# Digital_Clock_Backup_SCH.net
KiCad netlist of a schematic drawn in Altium Designer
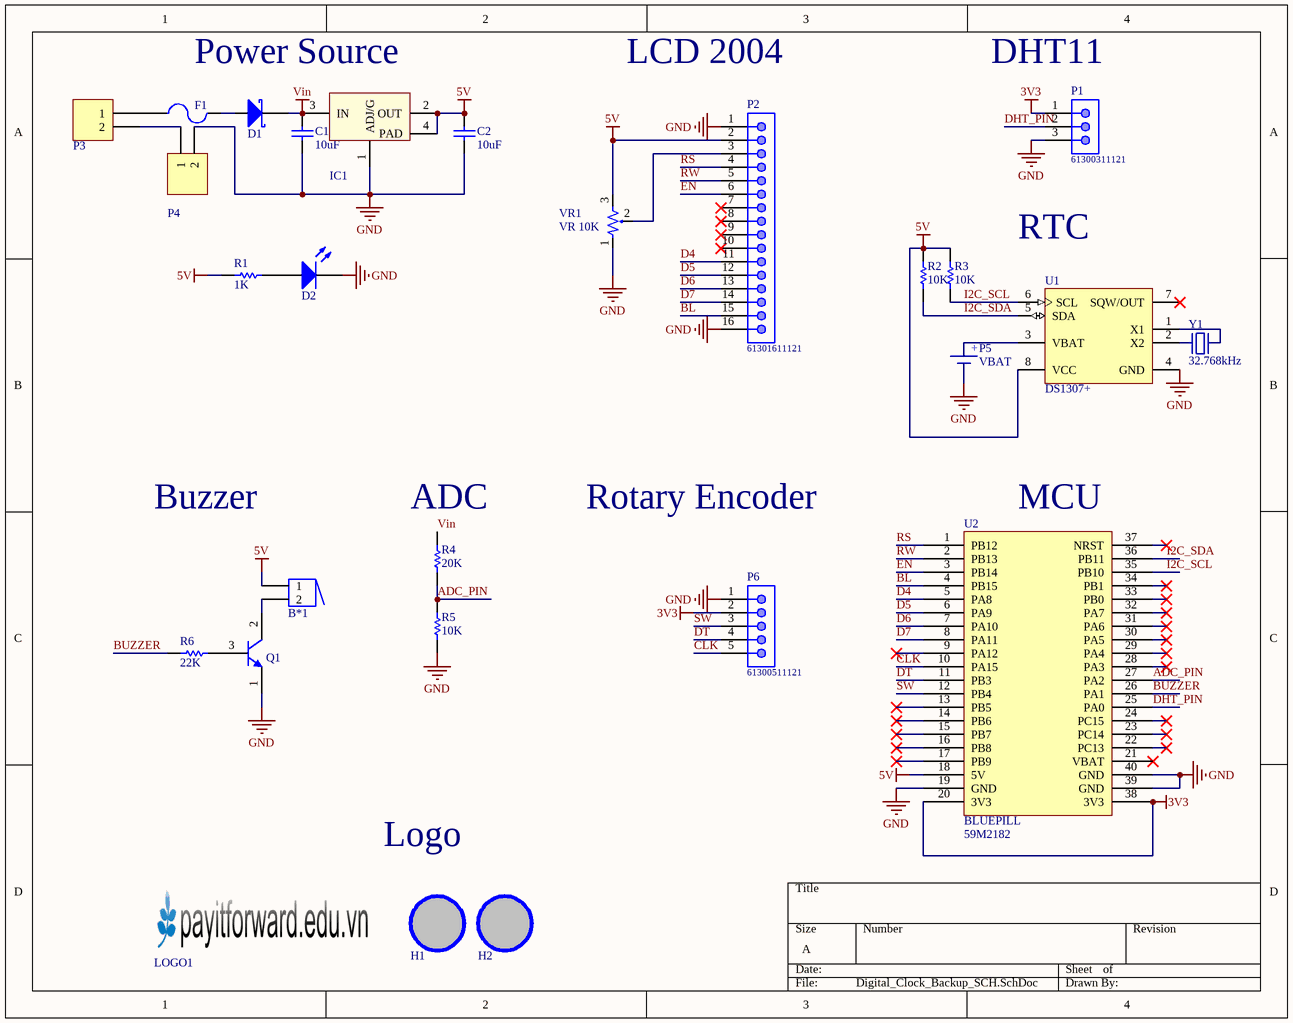
[diagram p0: Digital_Clock_Backup_SCH.SchDoc]

(export (version "E")
  (design (tool "Eeschema 10.0.6"))
  (components
    (comp (ref "B*1") (value "Buzzer") (footprint "BUZZER") (libsource (lib "PIF_Library") (part "Buzzer")))
    (comp (ref "C1")
      (value "10uF")
      (footprint "CAP-SM-0805")
      (description "Capacitor")
      (fields (field (name "Comment") "Cap Non-Pol SMD"))
      (libsource (lib "PIF_Library") (part "Cap Non-Pol SMD"))
    )
    (comp (ref "C2")
      (value "10uF")
      (footprint "CAP-SM-0805")
      (description "Capacitor")
      (fields (field (name "Comment") "Cap Non-Pol SMD"))
      (libsource (lib "PIF_Library") (part "Cap Non-Pol SMD"))
    )
    (comp (ref "D1")
      (value "D Schottky")
      (footprint "SS34")
      (description "Schottky Diode")
      (fields (field (name "PUBLISHER") "Altium Limited"))
      (libsource (lib "PIF_Library") (part "D Schottky"))
    )
    (comp (ref "D2") (value "LED") (footprint "LED-3mm") (libsource (lib "PIF_Library") (part "LED")))
    (comp (ref "F1") (value "Fuse") (footprint "FUSE SMD") (libsource (lib "PIF_Library") (part "Fuse")))
    (comp (ref "H1")
      (value "Hole")
      (footprint "LO KHOAN 3MM")
      (description "Hole 3mm")
      (libsource (lib "PIF_Library") (part "Hole"))
    )
    (comp (ref "H2")
      (value "Hole")
      (footprint "LO KHOAN 3MM")
      (description "Hole 3mm")
      (libsource (lib "PIF_Library") (part "Hole"))
    )
    (comp (ref "IC1")
      (value "LM1117")
      (footprint "SOT223-4N")
      (description "Available in 1.8V, 2.5V, 2.85V, 3.3V, 5V, and  Adjustable Versions")
      (libsource (lib "PIF_Library") (part "LM1117"))
    )
    (comp (ref "LOGO1")
      (value "LOGO PIF")
      (footprint "PIF LOGO SMALL TOP")
      (libsource (lib "PIF_Library") (part "LOGO PIF"))
    )
    (comp (ref "P1")
      (value "61300311121")
      (footprint "61300311121")
      (description "WR-PHD Pin Header, THT, pitch 2.54mm, Single Row, Vertical, 3p")
      (fields (field (name "MANUFACTURER") "Wurth Elektronik"))
      (libsource (lib "Altium_WR-PHD (rev20a)") (part "61300311121"))
    )
    (comp (ref "P2")
      (value "61301611121")
      (footprint "61301611121")
      (description "WR-PHD Pin Header, THT, pitch 2.54mm, Single Row, Vertical, 16p")
      (fields (field (name "MANUFACTURER") "Wurth Elektronik"))
      (libsource (lib "Altium_WR-PHD (rev20a)") (part "61301611121"))
    )
    (comp (ref "P3")
      (value "Domino 2")
      (footprint "DOMINO SMALL 2")
      (description "Domino, 2-Pin")
      (fields (field (name "PUBLISHER") "Altium Limited"))
      (libsource (lib "PIF_Library") (part "Domino 2"))
    )
    (comp (ref "P4")
      (value "Domino 2")
      (footprint "DOMINO SMALL 2")
      (description "Domino, 2-Pin")
      (fields (field (name "PUBLISHER") "Altium Limited"))
      (libsource (lib "") (part "Domino 2_1"))
    )
    (comp (ref "P5")
      (value "VBAT")
      (footprint "VBAT CR2030")
      (description "CR2032")
      (fields
        (field (name "MANUFACTURER") "DANTONA INDUSTRIES")
        (field (name "MANUFACTURER PART NUMBER") "CR2032 SANYO")
      )
      (libsource (lib "Digital_Clock") (part "VBAT CR2032"))
    )
    (comp (ref "P6")
      (value "61300511121")
      (footprint "61300511121")
      (description "WR-PHD Pin Header, THT, pitch 2.54mm, Single Row, Vertical, 5p")
      (fields (field (name "MANUFACTURER") "Wurth Elektronik"))
      (libsource (lib "Altium_WR-PHD (rev20a)") (part "61300511121"))
    )
    (comp (ref "Q1")
      (value "C1815")
      (footprint "SOT23B")
      (description "NPN Bipolar Transistor")
      (libsource (lib "PIF_Library") (part "C1815"))
    )
    (comp (ref "R1")
      (value "1K")
      (footprint "RES-SM-0805")
      (description "Resistor")
      (fields (field (name "Comment") "RESISTOR SMD"))
      (libsource (lib "PIF_Library") (part "RESISTOR SMD"))
    )
    (comp (ref "R2")
      (value "10K")
      (footprint "RES-SM-0805")
      (description "Resistor")
      (fields (field (name "Comment") "RESISTOR SMD"))
      (libsource (lib "PIF_Library") (part "RESISTOR SMD"))
    )
    (comp (ref "R3")
      (value "10K")
      (footprint "RES-SM-0805")
      (description "Resistor")
      (fields (field (name "Comment") "RESISTOR SMD"))
      (libsource (lib "PIF_Library") (part "RESISTOR SMD"))
    )
    (comp (ref "R4")
      (value "20K")
      (footprint "RES-SM-0805")
      (description "Resistor")
      (fields (field (name "Comment") "RESISTOR SMD"))
      (libsource (lib "PIF_Library") (part "RESISTOR SMD"))
    )
    (comp (ref "R5")
      (value "10K")
      (footprint "RES-SM-0805")
      (description "Resistor")
      (fields (field (name "Comment") "RESISTOR SMD"))
      (libsource (lib "PIF_Library") (part "RESISTOR SMD"))
    )
    (comp (ref "R6")
      (value "22K")
      (footprint "RES-SM-0805")
      (description "Resistor")
      (fields (field (name "Comment") "RESISTOR SMD"))
      (libsource (lib "PIF_Library") (part "RESISTOR SMD"))
    )
    (comp (ref "U1")
      (value "DS1307+")
      (footprint "MAXM-P8-1")
      (description "I2C Real-Time Clock, 5 V, 0 to 70 degC, 8-Pin DIP, RoHS, Tube")
      (fields (field (name "MANUFACTURER") "Maxim"))
      (libsource (lib "HCMUT") (part "MAXM-DS1307Z+-8"))
    )
    (comp (ref "U2")
      (value "BLUEPILL")
      (footprint "BLUEPILL")
      (description "Development board STM32F103C8T6")
      (fields (field (name "SUPPLIER PART NUMBER 1") "59M2182"))
      (libsource (lib "Giang's Libs") (part "BLUEPILL"))
    )
    (comp (ref "VR1")
      (value "VR 10K")
      (footprint "Varistor 1")
      (description "Var Resistor")
      (fields (field (name "Comment") "10K"))
      (libsource (lib "PIF_Library") (part "Var Resistor"))
    )
    (comp (ref "Y1")
      (value "32.768kHz")
      (footprint "XTAL 32768 3x8")
      (description "Crystal For all Crystal 2pin")
      (libsource (lib "Digital_Clock") (part "XTAL"))
    )
  )
  (nets
    (net (code "1") (name "/ADC_PIN") (class "Default")
      (node (ref "R4") (pin "1") (pinfunction "1_1") (pintype "passive"))
      (node (ref "R5") (pin "2") (pinfunction "2_2") (pintype "passive"))
      (node (ref "U2") (pin "27") (pinfunction "PA2_27") (pintype "passive"))
    )
    (net (code "2") (name "/BL") (class "Default")
      (node (ref "P2") (pin "15") (pinfunction "15_15") (pintype "passive"))
      (node (ref "U2") (pin "4") (pinfunction "PB15_4") (pintype "passive"))
    )
    (net (code "3") (name "/BUZZER") (class "Default")
      (node (ref "R6") (pin "1") (pinfunction "1_1") (pintype "passive"))
      (node (ref "U2") (pin "26") (pinfunction "PA1_26") (pintype "passive"))
    )
    (net (code "4") (name "/CLK") (class "Default")
      (node (ref "P6") (pin "5") (pinfunction "5_5") (pintype "passive"))
      (node (ref "U2") (pin "10") (pinfunction "PA15_10") (pintype "passive"))
    )
    (net (code "5") (name "/D4") (class "Default")
      (node (ref "P2") (pin "11") (pinfunction "11_11") (pintype "passive"))
      (node (ref "U2") (pin "5") (pinfunction "PA8_5") (pintype "passive"))
    )
    (net (code "6") (name "/D5") (class "Default")
      (node (ref "P2") (pin "12") (pinfunction "12_12") (pintype "passive"))
      (node (ref "U2") (pin "6") (pinfunction "PA9_6") (pintype "passive"))
    )
    (net (code "7") (name "/D6") (class "Default")
      (node (ref "P2") (pin "13") (pinfunction "13_13") (pintype "passive"))
      (node (ref "U2") (pin "7") (pinfunction "PA10_7") (pintype "passive"))
    )
    (net (code "8") (name "/D7") (class "Default")
      (node (ref "P2") (pin "14") (pinfunction "14_14") (pintype "passive"))
      (node (ref "U2") (pin "8") (pinfunction "PA11_8") (pintype "passive"))
    )
    (net (code "9") (name "/DHT_PIN") (class "Default")
      (node (ref "P1") (pin "2") (pinfunction "2_2") (pintype "passive"))
      (node (ref "U2") (pin "25") (pinfunction "PA0_25") (pintype "passive"))
    )
    (net (code "10") (name "/DT") (class "Default")
      (node (ref "P6") (pin "4") (pinfunction "4_4") (pintype "passive"))
      (node (ref "U2") (pin "11") (pinfunction "PB3_11") (pintype "passive"))
    )
    (net (code "11") (name "/EN") (class "Default")
      (node (ref "P2") (pin "6") (pinfunction "6_6") (pintype "passive"))
      (node (ref "U2") (pin "3") (pinfunction "PB14_3") (pintype "passive"))
    )
    (net (code "12") (name "/I2C_SCL") (class "Default")
      (node (ref "R3") (pin "1") (pinfunction "1_1") (pintype "passive"))
      (node (ref "U1") (pin "6") (pinfunction "SCL_6") (pintype "input"))
      (node (ref "U2") (pin "35") (pinfunction "PB10_35") (pintype "passive"))
    )
    (net (code "13") (name "/I2C_SDA") (class "Default")
      (node (ref "R2") (pin "1") (pinfunction "1_1") (pintype "passive"))
      (node (ref "U1") (pin "5") (pinfunction "SDA_5") (pintype "bidirectional"))
      (node (ref "U2") (pin "36") (pinfunction "PB11_36") (pintype "passive"))
    )
    (net (code "14") (name "/RS") (class "Default")
      (node (ref "P2") (pin "4") (pinfunction "4_4") (pintype "passive"))
      (node (ref "U2") (pin "1") (pinfunction "PB12_1") (pintype "passive"))
    )
    (net (code "15") (name "/RW") (class "Default")
      (node (ref "P2") (pin "5") (pinfunction "5_5") (pintype "passive"))
      (node (ref "U2") (pin "2") (pinfunction "PB13_2") (pintype "passive"))
    )
    (net (code "16") (name "/SW") (class "Default")
      (node (ref "P6") (pin "3") (pinfunction "3_3") (pintype "passive"))
      (node (ref "U2") (pin "12") (pinfunction "PB4_12") (pintype "passive"))
    )
    (net (code "17") (name "3V3") (class "Default")
      (node (ref "P1") (pin "1") (pinfunction "1_1") (pintype "passive"))
      (node (ref "P6") (pin "2") (pinfunction "2_2") (pintype "passive"))
      (node (ref "U2") (pin "20") (pinfunction "3V3_20") (pintype "passive"))
      (node (ref "U2") (pin "38") (pinfunction "3V3_38") (pintype "passive"))
    )
    (net (code "18") (name "5V") (class "Default")
      (node (ref "B*1") (pin "1") (pinfunction "1_1") (pintype "passive"))
      (node (ref "C2") (pin "2") (pinfunction "2_2") (pintype "passive"))
      (node (ref "IC1") (pin "2") (pinfunction "OUT_2") (pintype "passive"))
      (node (ref "IC1") (pin "4") (pinfunction "PAD_4") (pintype "passive"))
      (node (ref "P2") (pin "2") (pinfunction "2_2") (pintype "passive"))
      (node (ref "R1") (pin "1") (pinfunction "1_1") (pintype "passive"))
      (node (ref "R2") (pin "2") (pinfunction "2_2") (pintype "passive"))
      (node (ref "R3") (pin "2") (pinfunction "2_2") (pintype "passive"))
      (node (ref "U1") (pin "8") (pinfunction "VCC_8") (pintype "power_in"))
      (node (ref "U2") (pin "18") (pinfunction "5V_18") (pintype "passive"))
      (node (ref "VR1") (pin "3") (pinfunction "3_3") (pintype "passive"))
    )
    (net (code "19") (name "GND") (class "Default")
      (node (ref "C1") (pin "1") (pinfunction "1_1") (pintype "passive"))
      (node (ref "C2") (pin "1") (pinfunction "1_1") (pintype "passive"))
      (node (ref "D2") (pin "2") (pinfunction "K_2") (pintype "passive"))
      (node (ref "IC1") (pin "1") (pinfunction "ADJ/G_1") (pintype "passive"))
      (node (ref "P1") (pin "3") (pinfunction "3_3") (pintype "passive"))
      (node (ref "P2") (pin "1") (pinfunction "1_1") (pintype "passive"))
      (node (ref "P2") (pin "16") (pinfunction "16_16") (pintype "passive"))
      (node (ref "P4") (pin "2") (pinfunction "2_2") (pintype "passive"))
      (node (ref "P5") (pin "2") (pinfunction "+_2") (pintype "passive"))
      (node (ref "P6") (pin "1") (pinfunction "1_1") (pintype "passive"))
      (node (ref "Q1") (pin "1") (pinfunction "E_1") (pintype "passive"))
      (node (ref "R5") (pin "1") (pinfunction "1_1") (pintype "passive"))
      (node (ref "U1") (pin "4") (pinfunction "GND_4") (pintype "power_in"))
      (node (ref "U2") (pin "19") (pinfunction "GND_19") (pintype "passive"))
      (node (ref "U2") (pin "39") (pinfunction "GND_39") (pintype "passive"))
      (node (ref "U2") (pin "40") (pinfunction "GND_40") (pintype "passive"))
      (node (ref "VR1") (pin "1") (pinfunction "1_1") (pintype "passive"))
    )
    (net (code "20") (name "Net-(D1-A)") (class "Default")
      (node (ref "D1") (pin "1") (pinfunction "A_1") (pintype "passive"))
      (node (ref "F1") (pin "2") (pinfunction "2_2") (pintype "passive"))
    )
    (net (code "21") (name "Net-(D2-A)") (class "Default")
      (node (ref "D2") (pin "1") (pinfunction "A_1") (pintype "passive"))
      (node (ref "R1") (pin "2") (pinfunction "2_2") (pintype "passive"))
    )
    (net (code "22") (name "Net-(F1-Pad1)") (class "Default")
      (node (ref "F1") (pin "1") (pinfunction "1_1") (pintype "passive"))
      (node (ref "P3") (pin "1") (pinfunction "1_1") (pintype "passive"))
    )
    (net (code "23") (name "Net-(P2-Pad3)") (class "Default")
      (node (ref "P2") (pin "3") (pinfunction "3_3") (pintype "passive"))
      (node (ref "VR1") (pin "2") (pinfunction "2_2") (pintype "passive"))
    )
    (net (code "24") (name "Net-(P3-Pad2)") (class "Default")
      (node (ref "P3") (pin "2") (pinfunction "2_2") (pintype "passive"))
      (node (ref "P4") (pin "1") (pinfunction "1_1") (pintype "passive"))
    )
    (net (code "25") (name "Net-(Q1-B)") (class "Default")
      (node (ref "Q1") (pin "3") (pinfunction "B_3") (pintype "passive"))
      (node (ref "R6") (pin "2") (pinfunction "2_2") (pintype "passive"))
    )
    (net (code "26") (name "Net-(Q1-C)") (class "Default")
      (node (ref "B*1") (pin "2") (pinfunction "2_2") (pintype "passive"))
      (node (ref "Q1") (pin "2") (pinfunction "C_2") (pintype "passive"))
    )
    (net (code "27") (name "Net-(U1-VBAT)") (class "Default")
      (node (ref "P5") (pin "1") (pinfunction "+_1") (pintype "passive"))
      (node (ref "U1") (pin "3") (pinfunction "VBAT_3") (pintype "power_in"))
    )
    (net (code "28") (name "Net-(U1-X1)") (class "Default")
      (node (ref "U1") (pin "1") (pinfunction "X1_1") (pintype "passive"))
      (node (ref "Y1") (pin "2") (pinfunction "2_2") (pintype "passive"))
    )
    (net (code "29") (name "Net-(U1-X2)") (class "Default")
      (node (ref "U1") (pin "2") (pinfunction "X2_2") (pintype "passive"))
      (node (ref "Y1") (pin "1") (pinfunction "1_1") (pintype "passive"))
    )
    (net (code "30") (name "Vin") (class "Default")
      (node (ref "C1") (pin "2") (pinfunction "2_2") (pintype "passive"))
      (node (ref "D1") (pin "2") (pinfunction "K_2") (pintype "passive"))
      (node (ref "IC1") (pin "3") (pinfunction "IN_3") (pintype "passive"))
      (node (ref "R4") (pin "2") (pinfunction "2_2") (pintype "passive"))
    )
    (net (code "31") (name "unconnected-(H1-Pad1)") (class "Default")
      (node (ref "H1") (pin "1") (pinfunction "1_1") (pintype "passive"))
    )
    (net (code "32") (name "unconnected-(H2-Pad1)") (class "Default")
      (node (ref "H2") (pin "1") (pinfunction "1_1") (pintype "passive"))
    )
    (net (code "33") (name "unconnected-(P2-Pad7)") (class "Default")
      (node (ref "P2") (pin "7") (pinfunction "7_7") (pintype "passive+no_connect"))
    )
    (net (code "34") (name "unconnected-(P2-Pad8)") (class "Default")
      (node (ref "P2") (pin "8") (pinfunction "8_8") (pintype "passive+no_connect"))
    )
    (net (code "35") (name "unconnected-(P2-Pad9)") (class "Default")
      (node (ref "P2") (pin "9") (pinfunction "9_9") (pintype "passive+no_connect"))
    )
    (net (code "36") (name "unconnected-(P2-Pad10)") (class "Default")
      (node (ref "P2") (pin "10") (pinfunction "10_10") (pintype "passive+no_connect"))
    )
    (net (code "37") (name "unconnected-(U1-SQW{slash}OUT-Pad7)") (class "Default")
      (node (ref "U1") (pin "7") (pinfunction "SQW/OUT_7") (pintype "open_collector+no_connect"))
    )
    (net (code "38") (name "unconnected-(U2-NRST-Pad37)") (class "Default")
      (node (ref "U2") (pin "37") (pinfunction "NRST_37") (pintype "passive+no_connect"))
    )
    (net (code "39") (name "unconnected-(U2-PA3-Pad28)") (class "Default")
      (node (ref "U2") (pin "28") (pinfunction "PA3_28") (pintype "passive+no_connect"))
    )
    (net (code "40") (name "unconnected-(U2-PA4-Pad29)") (class "Default")
      (node (ref "U2") (pin "29") (pinfunction "PA4_29") (pintype "passive+no_connect"))
    )
    (net (code "41") (name "unconnected-(U2-PA5-Pad30)") (class "Default")
      (node (ref "U2") (pin "30") (pinfunction "PA5_30") (pintype "passive+no_connect"))
    )
    (net (code "42") (name "unconnected-(U2-PA6-Pad31)") (class "Default")
      (node (ref "U2") (pin "31") (pinfunction "PA6_31") (pintype "passive+no_connect"))
    )
    (net (code "43") (name "unconnected-(U2-PA7-Pad32)") (class "Default")
      (node (ref "U2") (pin "32") (pinfunction "PA7_32") (pintype "passive+no_connect"))
    )
    (net (code "44") (name "unconnected-(U2-PA12-Pad9)") (class "Default")
      (node (ref "U2") (pin "9") (pinfunction "PA12_9") (pintype "passive+no_connect"))
    )
    (net (code "45") (name "unconnected-(U2-PB0-Pad33)") (class "Default")
      (node (ref "U2") (pin "33") (pinfunction "PB0_33") (pintype "passive+no_connect"))
    )
    (net (code "46") (name "unconnected-(U2-PB1-Pad34)") (class "Default")
      (node (ref "U2") (pin "34") (pinfunction "PB1_34") (pintype "passive+no_connect"))
    )
    (net (code "47") (name "unconnected-(U2-PB5-Pad13)") (class "Default")
      (node (ref "U2") (pin "13") (pinfunction "PB5_13") (pintype "passive+no_connect"))
    )
    (net (code "48") (name "unconnected-(U2-PB6-Pad14)") (class "Default")
      (node (ref "U2") (pin "14") (pinfunction "PB6_14") (pintype "passive+no_connect"))
    )
    (net (code "49") (name "unconnected-(U2-PB7-Pad15)") (class "Default")
      (node (ref "U2") (pin "15") (pinfunction "PB7_15") (pintype "passive+no_connect"))
    )
    (net (code "50") (name "unconnected-(U2-PB8-Pad16)") (class "Default")
      (node (ref "U2") (pin "16") (pinfunction "PB8_16") (pintype "passive+no_connect"))
    )
    (net (code "51") (name "unconnected-(U2-PB9-Pad17)") (class "Default")
      (node (ref "U2") (pin "17") (pinfunction "PB9_17") (pintype "passive+no_connect"))
    )
    (net (code "52") (name "unconnected-(U2-PC13-Pad22)") (class "Default")
      (node (ref "U2") (pin "22") (pinfunction "PC13_22") (pintype "passive+no_connect"))
    )
    (net (code "53") (name "unconnected-(U2-PC14-Pad23)") (class "Default")
      (node (ref "U2") (pin "23") (pinfunction "PC14_23") (pintype "passive+no_connect"))
    )
    (net (code "54") (name "unconnected-(U2-PC15-Pad24)") (class "Default")
      (node (ref "U2") (pin "24") (pinfunction "PC15_24") (pintype "passive+no_connect"))
    )
    (net (code "55") (name "unconnected-(U2-VBAT-Pad21)") (class "Default")
      (node (ref "U2") (pin "21") (pinfunction "VBAT_21") (pintype "passive+no_connect"))
    )
  )
)
